# nanomodem.net
KiCad netlist of a schematic drawn in EAGLE
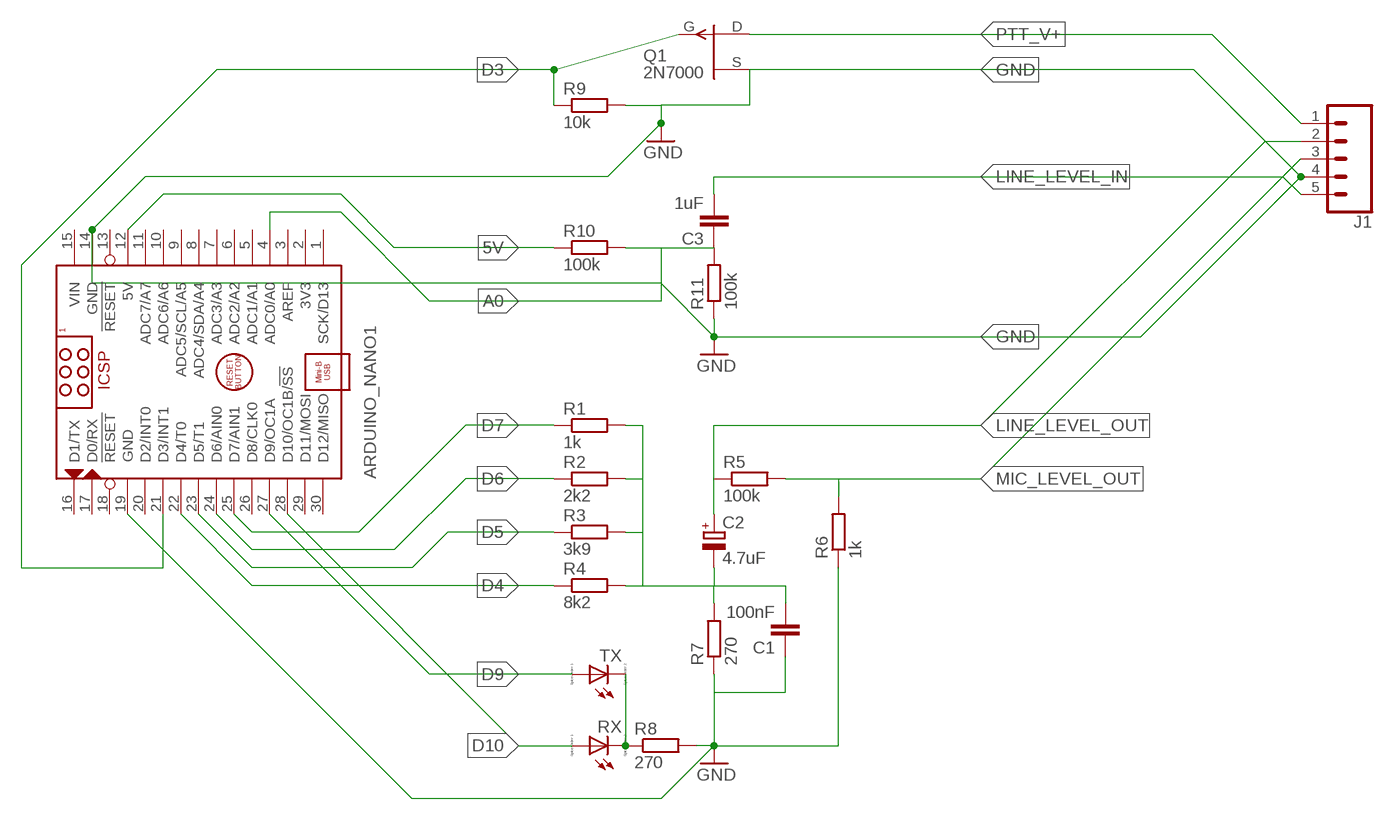
[diagram p0: schematic, sheet 1]

(export (version "E")
  (design (tool "Eeschema 10.0.6"))
  (components
    (comp (ref "ARDUINO_NANO1")
      (value "ARDUINO_NANO")
      (footprint "eagle-import:ARDUINO_NANO")
      (libsource (lib "eagle-import") (part "ARDUINO_NANO"))
    )
    (comp (ref "C1")
      (value "100nF")
      (footprint "eagle-import:C2.5-2")
      (libsource (lib "eagle-import") (part "C2.5/2"))
    )
    (comp (ref "C2")
      (value "4.7uF")
      (footprint "eagle-import:E2,5-4R")
      (libsource (lib "eagle-import") (part "CPOL-EUE2.5-5V"))
    )
    (comp (ref "C3")
      (value "1uF")
      (footprint "eagle-import:C2.5-2")
      (libsource (lib "eagle-import") (part "C2.5/2"))
    )
    (comp (ref "J1")
      (value "CONN_05")
      (footprint "eagle-import:1X05")
      (libsource (lib "eagle-import") (part "CONN_05"))
    )
    (comp (ref "Q1")
      (value "2N7000")
      (footprint "eagle-import:TO92_MOD")
      (libsource (lib "eagle-import") (part "2N3820"))
    )
    (comp (ref "R1")
      (value "1k")
      (footprint "eagle-import:0204V")
      (libsource (lib "eagle-import") (part "resistor_R-EU_0204/2V"))
    )
    (comp (ref "R2")
      (value "2k2")
      (footprint "eagle-import:0204V")
      (libsource (lib "eagle-import") (part "resistor_R-EU_0204/2V"))
    )
    (comp (ref "R3")
      (value "3k9")
      (footprint "eagle-import:0204V")
      (libsource (lib "eagle-import") (part "resistor_R-EU_0204/2V"))
    )
    (comp (ref "R4")
      (value "8k2")
      (footprint "eagle-import:0204V")
      (libsource (lib "eagle-import") (part "resistor_R-EU_0204/2V"))
    )
    (comp (ref "R5")
      (value "100k")
      (footprint "eagle-import:0204V")
      (libsource (lib "eagle-import") (part "resistor_R-EU_0204/2V"))
    )
    (comp (ref "R6")
      (value "1k")
      (footprint "eagle-import:0204V")
      (libsource (lib "eagle-import") (part "resistor_R-EU_0204/2V"))
    )
    (comp (ref "R7")
      (value "270")
      (footprint "eagle-import:0204V")
      (libsource (lib "eagle-import") (part "resistor_R-EU_0204/2V"))
    )
    (comp (ref "R8")
      (value "270")
      (footprint "eagle-import:0204V")
      (libsource (lib "eagle-import") (part "resistor_R-EU_0204/2V"))
    )
    (comp (ref "R9")
      (value "10k")
      (footprint "eagle-import:0204V")
      (libsource (lib "eagle-import") (part "R-EU_0204/2V"))
    )
    (comp (ref "R10")
      (value "100k")
      (footprint "eagle-import:0204V")
      (libsource (lib "eagle-import") (part "R-EU_0204/2V"))
    )
    (comp (ref "R11")
      (value "100k")
      (footprint "eagle-import:0204V")
      (libsource (lib "eagle-import") (part "R-EU_0204/2V"))
    )
    (comp (ref "RX")
      (value "LED_ELD260")
      (footprint "eagle-import:LED_LD260")
      (libsource (lib "eagle-import") (part "LED_ELD260"))
    )
    (comp (ref "TX")
      (value "LED_ELD260")
      (footprint "eagle-import:LED_LD260")
      (libsource (lib "eagle-import") (part "LED_ELD260"))
    )
  )
  (nets
    (net (code "1") (name "/VIN") (class "Default")
      (node (ref "ARDUINO_NANO1") (pin "15") (pinfunction "VIN_15") (pintype "power_in"))
    )
    (net (code "2") (name "5V") (class "Default")
      (node (ref "ARDUINO_NANO1") (pin "12") (pinfunction "5V_12") (pintype "power_in"))
      (node (ref "R10") (pin "1") (pinfunction "1_1") (pintype "passive"))
    )
    (net (code "3") (name "A0") (class "Default")
      (node (ref "ARDUINO_NANO1") (pin "4") (pinfunction "ADC0/A0_4") (pintype "bidirectional"))
      (node (ref "C3") (pin "1") (pinfunction "1_1") (pintype "passive"))
      (node (ref "R10") (pin "2") (pinfunction "2_2") (pintype "passive"))
      (node (ref "R11") (pin "2") (pinfunction "2_2") (pintype "passive"))
    )
    (net (code "4") (name "D3") (class "Default")
      (node (ref "ARDUINO_NANO1") (pin "21") (pinfunction "D3/INT1_21") (pintype "bidirectional"))
      (node (ref "Q1") (pin "2") (pinfunction "G_2") (pintype "passive"))
      (node (ref "R9") (pin "1") (pinfunction "1_1") (pintype "passive"))
    )
    (net (code "5") (name "D4") (class "Default")
      (node (ref "ARDUINO_NANO1") (pin "22") (pinfunction "D4/T0_22") (pintype "bidirectional"))
      (node (ref "R4") (pin "1") (pinfunction "1_1") (pintype "passive"))
    )
    (net (code "6") (name "D5") (class "Default")
      (node (ref "ARDUINO_NANO1") (pin "23") (pinfunction "D5/T1_23") (pintype "bidirectional"))
      (node (ref "R3") (pin "1") (pinfunction "1_1") (pintype "passive"))
    )
    (net (code "7") (name "D6") (class "Default")
      (node (ref "ARDUINO_NANO1") (pin "24") (pinfunction "D6/AIN0_24") (pintype "bidirectional"))
      (node (ref "R2") (pin "1") (pinfunction "1_1") (pintype "passive"))
    )
    (net (code "8") (name "D7") (class "Default")
      (node (ref "ARDUINO_NANO1") (pin "25") (pinfunction "D7/AIN1_25") (pintype "bidirectional"))
      (node (ref "R1") (pin "1") (pinfunction "1_1") (pintype "passive"))
    )
    (net (code "9") (name "D9") (class "Default")
      (node (ref "ARDUINO_NANO1") (pin "27") (pinfunction "D9/OC1A_27") (pintype "bidirectional"))
      (node (ref "TX") (pin "A") (pinfunction "A_A") (pintype "passive"))
    )
    (net (code "10") (name "D10") (class "Default")
      (node (ref "ARDUINO_NANO1") (pin "28") (pinfunction "D10/OC1B/~{SS}_28") (pintype "bidirectional"))
      (node (ref "RX") (pin "A") (pinfunction "A_A") (pintype "passive"))
    )
    (net (code "11") (name "GND") (class "Default")
      (node (ref "ARDUINO_NANO1") (pin "14") (pinfunction "GND_14") (pintype "power_in"))
      (node (ref "ARDUINO_NANO1") (pin "19") (pinfunction "GND_19") (pintype "power_in"))
      (node (ref "C1") (pin "1") (pinfunction "1_1") (pintype "passive"))
      (node (ref "J1") (pin "4") (pinfunction "4_4") (pintype "passive"))
      (node (ref "Q1") (pin "3") (pinfunction "D_3") (pintype "passive"))
      (node (ref "R11") (pin "1") (pinfunction "1_1") (pintype "passive"))
      (node (ref "R6") (pin "1") (pinfunction "1_1") (pintype "passive"))
      (node (ref "R7") (pin "1") (pinfunction "1_1") (pintype "passive"))
      (node (ref "R8") (pin "2") (pinfunction "2_2") (pintype "passive"))
      (node (ref "R9") (pin "2") (pinfunction "2_2") (pintype "passive"))
    )
    (net (code "12") (name "LINE_LEVEL_IN") (class "Default")
      (node (ref "C3") (pin "2") (pinfunction "2_2") (pintype "passive"))
      (node (ref "J1") (pin "5") (pinfunction "5_5") (pintype "passive"))
    )
    (net (code "13") (name "LINE_LEVEL_OUT") (class "Default")
      (node (ref "C2") (pin "+") (pinfunction "+_+") (pintype "passive"))
      (node (ref "J1") (pin "2") (pinfunction "2_2") (pintype "passive"))
      (node (ref "R5") (pin "1") (pinfunction "1_1") (pintype "passive"))
    )
    (net (code "14") (name "MIC_LEVEL_OUT") (class "Default")
      (node (ref "J1") (pin "3") (pinfunction "3_3") (pintype "passive"))
      (node (ref "R5") (pin "2") (pinfunction "2_2") (pintype "passive"))
      (node (ref "R6") (pin "2") (pinfunction "2_2") (pintype "passive"))
    )
    (net (code "15") (name "Net-(C1-Pad2)") (class "Default")
      (node (ref "C1") (pin "2") (pinfunction "2_2") (pintype "passive"))
      (node (ref "C2") (pin "-") (pinfunction "-_-") (pintype "passive"))
      (node (ref "R1") (pin "2") (pinfunction "2_2") (pintype "passive"))
      (node (ref "R2") (pin "2") (pinfunction "2_2") (pintype "passive"))
      (node (ref "R3") (pin "2") (pinfunction "2_2") (pintype "passive"))
      (node (ref "R4") (pin "2") (pinfunction "2_2") (pintype "passive"))
      (node (ref "R7") (pin "2") (pinfunction "2_2") (pintype "passive"))
    )
    (net (code "16") (name "Net-(RX-C)") (class "Default")
      (node (ref "R8") (pin "1") (pinfunction "1_1") (pintype "passive"))
      (node (ref "RX") (pin "K") (pinfunction "C_K") (pintype "passive"))
      (node (ref "TX") (pin "K") (pinfunction "C_K") (pintype "passive"))
    )
    (net (code "17") (name "PTT_V+") (class "Default")
      (node (ref "J1") (pin "1") (pinfunction "1_1") (pintype "passive"))
      (node (ref "Q1") (pin "1") (pinfunction "S_1") (pintype "passive"))
    )
    (net (code "18") (name "unconnected-(ARDUINO_NANO1-3V3-Pad2)") (class "Default")
      (node (ref "ARDUINO_NANO1") (pin "2") (pinfunction "3V3_2") (pintype "output"))
    )
    (net (code "19") (name "unconnected-(ARDUINO_NANO1-ADC1{slash}A1-Pad5)") (class "Default")
      (node (ref "ARDUINO_NANO1") (pin "5") (pinfunction "ADC1/A1_5") (pintype "bidirectional"))
    )
    (net (code "20") (name "unconnected-(ARDUINO_NANO1-ADC2{slash}A2-Pad6)") (class "Default")
      (node (ref "ARDUINO_NANO1") (pin "6") (pinfunction "ADC2/A2_6") (pintype "bidirectional"))
    )
    (net (code "21") (name "unconnected-(ARDUINO_NANO1-ADC3{slash}A3-Pad7)") (class "Default")
      (node (ref "ARDUINO_NANO1") (pin "7") (pinfunction "ADC3/A3_7") (pintype "bidirectional"))
    )
    (net (code "22") (name "unconnected-(ARDUINO_NANO1-ADC4{slash}SDA{slash}A4-Pad8)") (class "Default")
      (node (ref "ARDUINO_NANO1") (pin "8") (pinfunction "ADC4/SDA/A4_8") (pintype "bidirectional"))
    )
    (net (code "23") (name "unconnected-(ARDUINO_NANO1-ADC5{slash}SCL{slash}A5-Pad9)") (class "Default")
      (node (ref "ARDUINO_NANO1") (pin "9") (pinfunction "ADC5/SCL/A5_9") (pintype "bidirectional"))
    )
    (net (code "24") (name "unconnected-(ARDUINO_NANO1-ADC6{slash}A6-Pad10)") (class "Default")
      (node (ref "ARDUINO_NANO1") (pin "10") (pinfunction "ADC6/A6_10") (pintype "bidirectional"))
    )
    (net (code "25") (name "unconnected-(ARDUINO_NANO1-ADC7{slash}A7-Pad11)") (class "Default")
      (node (ref "ARDUINO_NANO1") (pin "11") (pinfunction "ADC7/A7_11") (pintype "bidirectional"))
    )
    (net (code "26") (name "unconnected-(ARDUINO_NANO1-AREF-Pad3)") (class "Default")
      (node (ref "ARDUINO_NANO1") (pin "3") (pinfunction "AREF_3") (pintype "input"))
    )
    (net (code "27") (name "unconnected-(ARDUINO_NANO1-D0{slash}RX-Pad17)") (class "Default")
      (node (ref "ARDUINO_NANO1") (pin "17") (pinfunction "D0/RX_17") (pintype "bidirectional"))
    )
    (net (code "28") (name "unconnected-(ARDUINO_NANO1-D1{slash}TX-Pad16)") (class "Default")
      (node (ref "ARDUINO_NANO1") (pin "16") (pinfunction "D1/TX_16") (pintype "bidirectional"))
    )
    (net (code "29") (name "unconnected-(ARDUINO_NANO1-D2{slash}INT0-Pad20)") (class "Default")
      (node (ref "ARDUINO_NANO1") (pin "20") (pinfunction "D2/INT0_20") (pintype "bidirectional"))
    )
    (net (code "30") (name "unconnected-(ARDUINO_NANO1-D8{slash}CLK0-Pad26)") (class "Default")
      (node (ref "ARDUINO_NANO1") (pin "26") (pinfunction "D8/CLK0_26") (pintype "bidirectional"))
    )
    (net (code "31") (name "unconnected-(ARDUINO_NANO1-D11{slash}MOSI-Pad29)") (class "Default")
      (node (ref "ARDUINO_NANO1") (pin "29") (pinfunction "D11/MOSI_29") (pintype "bidirectional"))
    )
    (net (code "32") (name "unconnected-(ARDUINO_NANO1-D12{slash}MISO-Pad30)") (class "Default")
      (node (ref "ARDUINO_NANO1") (pin "30") (pinfunction "D12/MISO_30") (pintype "bidirectional"))
    )
    (net (code "33") (name "unconnected-(ARDUINO_NANO1-SCK{slash}D13-Pad1)") (class "Default")
      (node (ref "ARDUINO_NANO1") (pin "1") (pinfunction "SCK/D13_1") (pintype "bidirectional"))
    )
    (net (code "34") (name "unconnected-(ARDUINO_NANO1-~{RESET}-Pad13)") (class "Default")
      (node (ref "ARDUINO_NANO1") (pin "13") (pinfunction "~{RESET}_13") (pintype "input"))
    )
    (net (code "35") (name "unconnected-(ARDUINO_NANO1-~{RESET}-Pad18)") (class "Default")
      (node (ref "ARDUINO_NANO1") (pin "18") (pinfunction "~{RESET}_18") (pintype "input"))
    )
  )
)
